# STM32_F407.net
KiCad netlist of a schematic drawn in Altium Designer
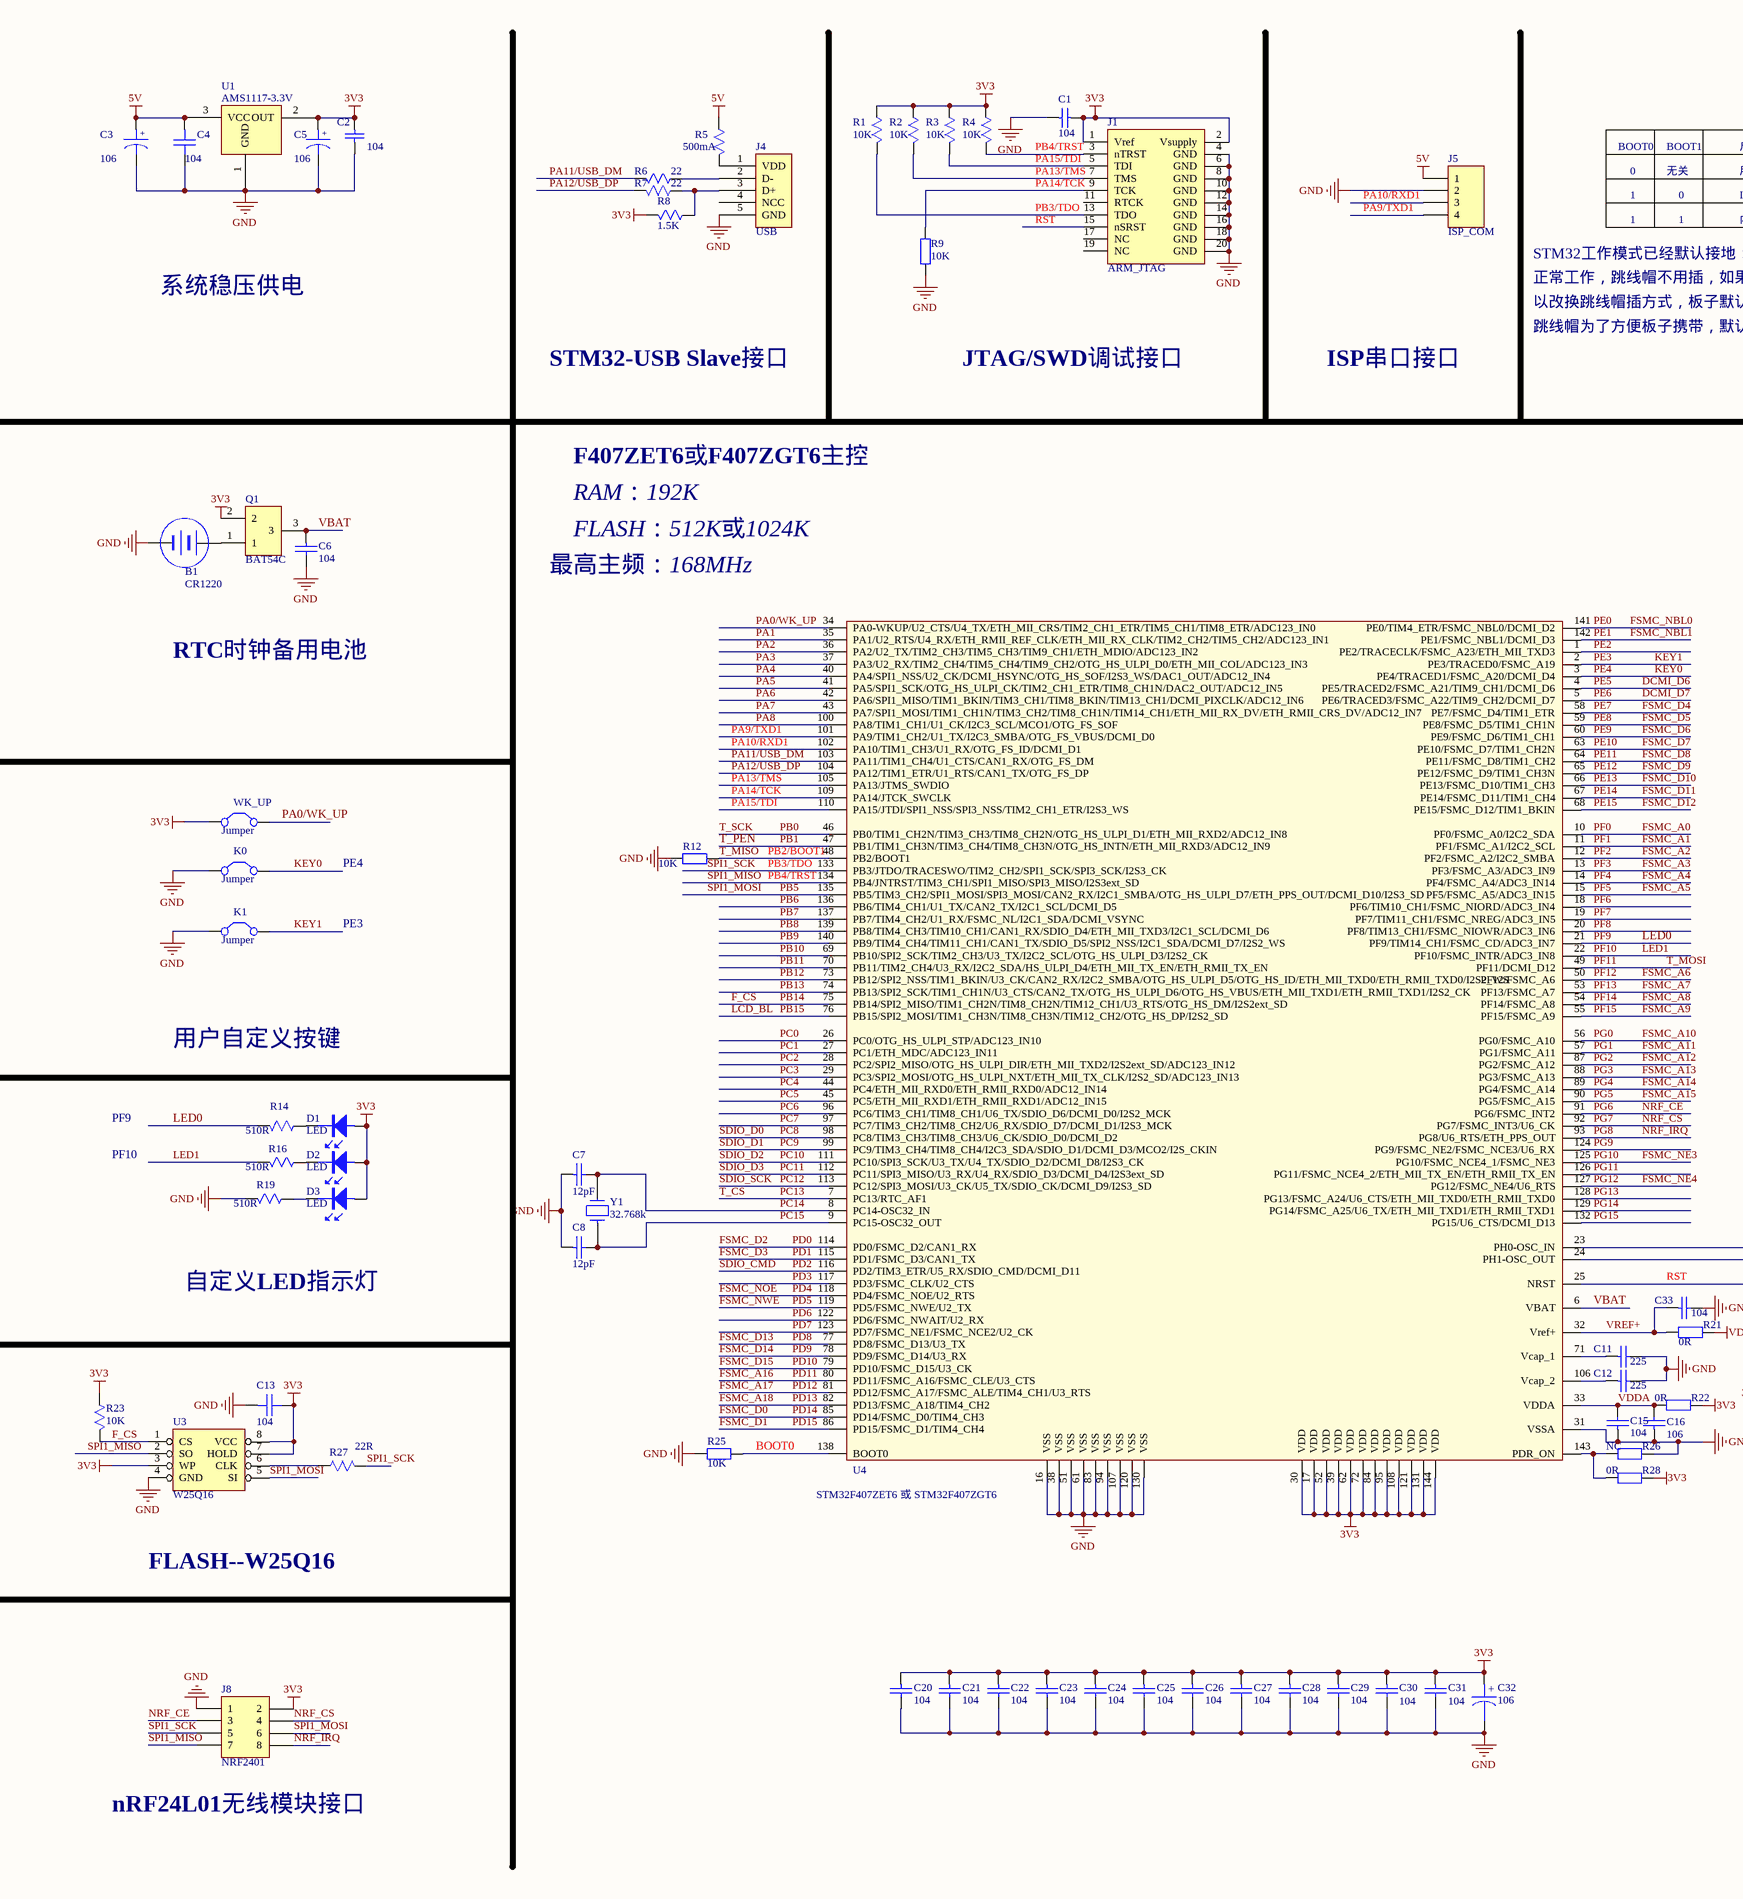
[diagram p0: STM32_F407.SchDoc, left]
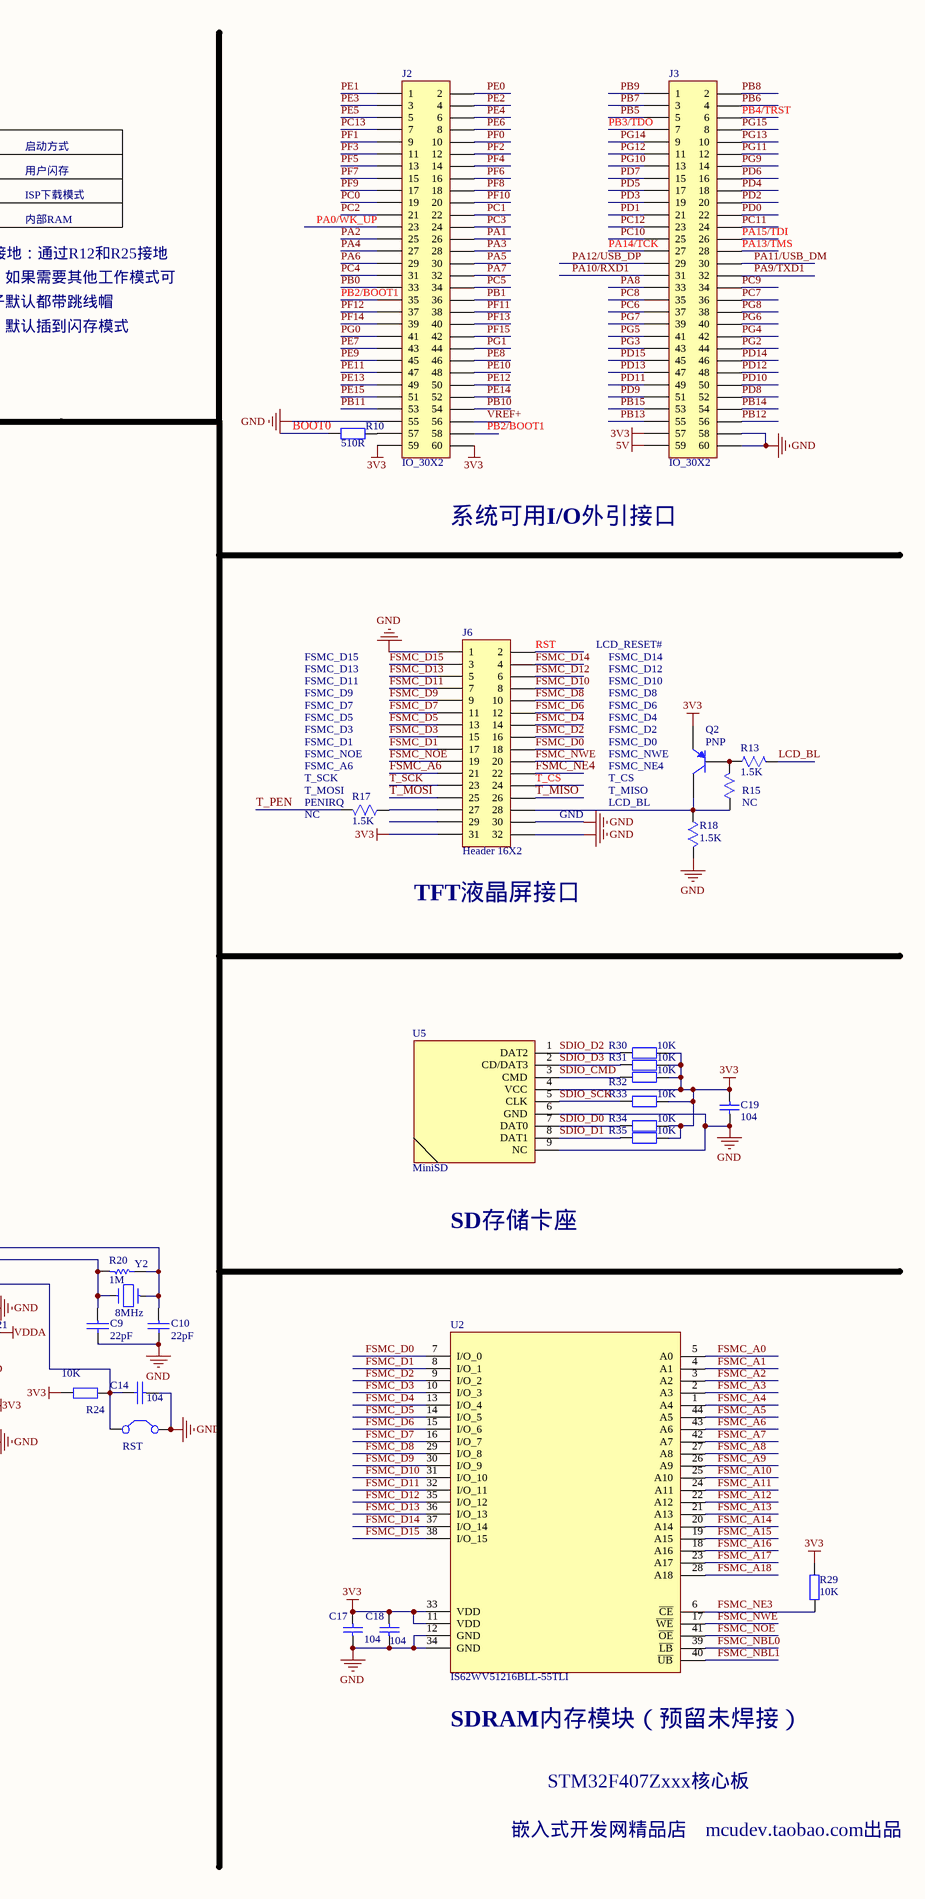
[diagram p1: STM32_F407.SchDoc, right]

(export (version "E")
  (design (tool "Eeschema 10.0.6"))
  (components
    (comp (ref "B1") (value "CR1220") (footprint "CP1220") (libsource (lib "YT1_SCH_99SE") (part "BATTERY")))
    (comp (ref "C1")
      (value "104")
      (footprint "RC0603")
      (description "Capacitor")
      (fields (field (name "PUBLISHER") "Altium Limited"))
      (libsource (lib "*") (part "Cap"))
    )
    (comp (ref "C2")
      (value "104")
      (footprint "RC0603")
      (description "Capacitor")
      (fields (field (name "PUBLISHER") "Altium Limited"))
      (libsource (lib "*") (part "Cap"))
    )
    (comp (ref "C3") (value "106") (footprint "RC0805") (libsource (lib "YT1_SCH_99SE") (part "CAP2")))
    (comp (ref "C4") (value "104") (footprint "RC0603") (libsource (lib "YT1_SCH_99SE") (part "CAP")))
    (comp (ref "C5") (value "106") (footprint "RC0805") (libsource (lib "YT1_SCH_99SE") (part "CAP2")))
    (comp (ref "C6")
      (value "104")
      (footprint "RC0603")
      (description "Capcitor")
      (libsource (lib "") (part "CAP_1"))
    )
    (comp (ref "C7")
      (value "12pF")
      (footprint "RC0603")
      (description "Capcitor")
      (libsource (lib "LXKJSJ") (part "CAP"))
    )
    (comp (ref "C8")
      (value "12pF")
      (footprint "RC0603")
      (description "Capcitor")
      (libsource (lib "LXKJSJ") (part "CAP"))
    )
    (comp (ref "C9")
      (value "22pF")
      (footprint "RC0603")
      (description "Capcitor")
      (libsource (lib "LXKJSJ") (part "CAP"))
    )
    (comp (ref "C10")
      (value "22pF")
      (footprint "RC0603")
      (description "Capcitor")
      (libsource (lib "LXKJSJ") (part "CAP"))
    )
    (comp (ref "C11")
      (value "225")
      (footprint "RC0805")
      (description "Capcitor")
      (libsource (lib "LXKJSJ") (part "CAP"))
    )
    (comp (ref "C12")
      (value "225")
      (footprint "RC0805")
      (description "Capcitor")
      (libsource (lib "LXKJSJ") (part "CAP"))
    )
    (comp (ref "C13") (value "104") (footprint "RC0603") (libsource (lib "YT1_SCH_99SE") (part "CAP")))
    (comp (ref "C14")
      (value "104")
      (footprint "RC0603")
      (description "Capcitor")
      (libsource (lib "LXKJSJ") (part "CAP"))
    )
    (comp (ref "C15")
      (value "104")
      (footprint "RC0603")
      (description "Capcitor")
      (libsource (lib "LXKJSJ") (part "CAP"))
    )
    (comp (ref "C16")
      (value "106")
      (footprint "RC0805")
      (description "Capcitor")
      (libsource (lib "LXKJSJ") (part "CAP"))
    )
    (comp (ref "C17")
      (value "104")
      (footprint "RC0603")
      (description "Capacitor")
      (fields (field (name "PUBLISHER") "Altium Limited"))
      (libsource (lib "*") (part "Cap"))
    )
    (comp (ref "C18")
      (value "104")
      (footprint "RC0603")
      (description "Capacitor")
      (fields (field (name "PUBLISHER") "Altium Limited"))
      (libsource (lib "*") (part "Cap"))
    )
    (comp (ref "C19")
      (value "104")
      (footprint "RC0603")
      (description "Capacitor (Semiconductor SIM Model)")
      (fields (field (name "PUBLISHER") "Altium Limited"))
      (libsource (lib "*") (part "Cap Semi"))
    )
    (comp (ref "C20")
      (value "104")
      (footprint "RC0603")
      (description "Capcitor")
      (libsource (lib "LXKJSJ") (part "CAP"))
    )
    (comp (ref "C21")
      (value "104")
      (footprint "RC0603")
      (description "Capcitor")
      (libsource (lib "LXKJSJ") (part "CAP"))
    )
    (comp (ref "C22")
      (value "104")
      (footprint "RC0603")
      (description "Capcitor")
      (libsource (lib "LXKJSJ") (part "CAP"))
    )
    (comp (ref "C23")
      (value "104")
      (footprint "RC0603")
      (description "Capcitor")
      (libsource (lib "LXKJSJ") (part "CAP"))
    )
    (comp (ref "C24")
      (value "104")
      (footprint "RC0603")
      (description "Capcitor")
      (libsource (lib "LXKJSJ") (part "CAP"))
    )
    (comp (ref "C25")
      (value "104")
      (footprint "RC0603")
      (description "Capcitor")
      (libsource (lib "LXKJSJ") (part "CAP"))
    )
    (comp (ref "C26")
      (value "104")
      (footprint "RC0603")
      (description "Capcitor")
      (libsource (lib "LXKJSJ") (part "CAP"))
    )
    (comp (ref "C27")
      (value "104")
      (footprint "RC0603")
      (description "Capcitor")
      (libsource (lib "LXKJSJ") (part "CAP"))
    )
    (comp (ref "C28")
      (value "104")
      (footprint "RC0603")
      (description "Capcitor")
      (libsource (lib "LXKJSJ") (part "CAP"))
    )
    (comp (ref "C29")
      (value "104")
      (footprint "RC0603")
      (description "Capcitor")
      (libsource (lib "LXKJSJ") (part "CAP"))
    )
    (comp (ref "C30")
      (value "104")
      (footprint "RC0603")
      (description "Capcitor")
      (libsource (lib "LXKJSJ") (part "CAP"))
    )
    (comp (ref "C31")
      (value "104")
      (footprint "RC0603")
      (description "Capcitor")
      (libsource (lib "LXKJSJ") (part "CAP"))
    )
    (comp (ref "C32")
      (value "106")
      (footprint "RC0805")
      (description "Capacitor")
      (libsource (lib "*") (part "CAPACITOR POL"))
    )
    (comp (ref "C33")
      (value "104")
      (footprint "RC0603")
      (description "Capcitor")
      (libsource (lib "LXKJSJ") (part "CAP"))
    )
    (comp (ref "D1") (value "LED") (footprint "LED0805") (libsource (lib "*") (part "LED")))
    (comp (ref "D2") (value "LED") (footprint "LED0805") (libsource (lib "*") (part "LED")))
    (comp (ref "D3") (value "LED") (footprint "LED0805") (libsource (lib "*") (part "LED")))
    (comp (ref "J1")
      (value "ARM_JTAG")
      (footprint "JTAG20P")
      (description "JTAG")
      (libsource (lib "LXKJSJ") (part "JTAG"))
    )
    (comp (ref "J2")
      (value "IO_30X2")
      (footprint "IDE2X30")
      (description "Header, 30-Pin, Dual row")
      (fields (field (name "PUBLISHER") "Altium Limited"))
      (libsource (lib "Miscellaneous Connectors") (part "Header 30X2"))
    )
    (comp (ref "J3")
      (value "IO_30X2")
      (footprint "IDE2X30")
      (description "Header, 30-Pin, Dual row")
      (fields (field (name "PUBLISHER") "Altium Limited"))
      (libsource (lib "Miscellaneous Connectors") (part "Header 30X2"))
    )
    (comp (ref "J4") (value "USB") (footprint "MINUSB") (libsource (lib "YT1_SCH_99SE") (part "usb")))
    (comp (ref "J5")
      (value "ISP_COM")
      (footprint "HDR1X4")
      (description "Header, 4-Pin")
      (fields (field (name "PUBLISHER") "Altium Limited"))
      (libsource (lib "Miscellaneous Connectors") (part "Header 4"))
    )
    (comp (ref "J6")
      (value "Header 16X2")
      (footprint "IDE2X16-2.54")
      (description "Header, 16-Pin, Dual row")
      (fields (field (name "PUBLISHER") "Altium Limited"))
      (libsource (lib "Miscellaneous Connectors") (part "Header 16X2"))
    )
    (comp (ref "J8")
      (value "NRF2401")
      (footprint "DIP2X4-2.54")
      (description "Header, 4-Pin, Dual row")
      (fields (field (name "PUBLISHER") "Altium Limited"))
      (libsource (lib "Miscellaneous Connectors") (part "Header 4X2"))
    )
    (comp (ref "K0")
      (value "Jumper")
      (footprint "key")
      (description "Jumper Wire")
      (fields (field (name "PUBLISHER") "Altium Limited"))
      (libsource (lib "Free Documents") (part "Jumper"))
    )
    (comp (ref "K1")
      (value "Jumper")
      (footprint "key")
      (description "Jumper Wire")
      (fields (field (name "PUBLISHER") "Altium Limited"))
      (libsource (lib "Free Documents") (part "Jumper"))
    )
    (comp (ref "Q1") (value "BAT54C") (footprint "BAT54C") (libsource (lib "Newcapec9263") (part "BAT54C")))
    (comp (ref "Q2")
      (value "PNP")
      (footprint "PNP_SOT23")
      (description "PNP Bipolar Transistor")
      (fields (field (name "PUBLISHER") "Altium Limited"))
      (libsource (lib "Miscellaneous Devices") (part "PNP"))
    )
    (comp (ref "R1") (value "10K") (footprint "RC0603") (libsource (lib "YT1_SCH_99SE") (part "RES")))
    (comp (ref "R2") (value "10K") (footprint "RC0603") (libsource (lib "YT1_SCH_99SE") (part "RES")))
    (comp (ref "R3") (value "10K") (footprint "RC0603") (libsource (lib "YT1_SCH_99SE") (part "RES")))
    (comp (ref "R4") (value "10K") (footprint "RC0603") (libsource (lib "YT1_SCH_99SE") (part "RES")))
    (comp (ref "R5") (value "500mA") (footprint "RC0805") (libsource (lib "YT1_SCH_99SE") (part "RES")))
    (comp (ref "R6") (value "22") (footprint "RC0603") (libsource (lib "YT1_SCH_99SE") (part "RES")))
    (comp (ref "R7") (value "22") (footprint "RC0603") (libsource (lib "YT1_SCH_99SE") (part "RES")))
    (comp (ref "R8") (value "1.5K") (footprint "RC0603") (libsource (lib "YT1_SCH_99SE") (part "RES")))
    (comp (ref "R9")
      (value "10K")
      (footprint "RC0603")
      (description "Resistor")
      (libsource (lib "") (part "Res2_2"))
    )
    (comp (ref "R10")
      (value "510R")
      (footprint "RC0603")
      (description "Resistor")
      (libsource (lib "") (part "Res2_3"))
    )
    (comp (ref "R12")
      (value "10K")
      (footprint "RC0603")
      (description "Resistor")
      (libsource (lib "") (part "Res2_3"))
    )
    (comp (ref "R13") (value "1.5K") (footprint "RC0603") (libsource (lib "YT1_SCH_99SE") (part "RES")))
    (comp (ref "R14") (value "510R") (footprint "RC0603") (libsource (lib "YT1_SCH_99SE") (part "RES")))
    (comp (ref "R15") (value "NC") (footprint "RC0603") (libsource (lib "YT1_SCH_99SE") (part "RES")))
    (comp (ref "R16") (value "510R") (footprint "RC0603") (libsource (lib "YT1_SCH_99SE") (part "RES")))
    (comp (ref "R17") (value "1.5K") (footprint "RC0603") (libsource (lib "YT1_SCH_99SE") (part "RES")))
    (comp (ref "R18") (value "1.5K") (footprint "RC0603") (libsource (lib "YT1_SCH_99SE") (part "RES")))
    (comp (ref "R19") (value "510R") (footprint "RC0603") (libsource (lib "YT1_SCH_99SE") (part "RES")))
    (comp (ref "R20")
      (value "1M")
      (footprint "RC0603")
      (description "Resistor")
      (libsource (lib "Miscellaneous Devices") (part "Res1"))
    )
    (comp (ref "R21")
      (value "0R")
      (footprint "RC0603")
      (description "Resistor")
      (libsource (lib "") (part "Res2_1"))
    )
    (comp (ref "R22")
      (value "0R")
      (footprint "RC0603")
      (description "Resistor")
      (libsource (lib "") (part "Res2_1"))
    )
    (comp (ref "R23") (value "10K") (footprint "RC0603") (libsource (lib "YT1_SCH_99SE") (part "RES")))
    (comp (ref "R24")
      (value "10K")
      (footprint "RC0603")
      (description "Resistor")
      (libsource (lib "") (part "Res2_3"))
    )
    (comp (ref "R25")
      (value "10K")
      (footprint "RC0603")
      (description "Resistor")
      (libsource (lib "Miscellaneous Devices") (part "Res2"))
    )
    (comp (ref "R26")
      (value "NC")
      (footprint "RC0603")
      (description "Resistor")
      (libsource (lib "") (part "Res2_1"))
    )
    (comp (ref "R27") (value "22R") (footprint "RC0603") (libsource (lib "YT1_SCH_99SE") (part "RES")))
    (comp (ref "R28")
      (value "0R")
      (footprint "RC0603")
      (description "Resistor")
      (libsource (lib "") (part "Res2_1"))
    )
    (comp (ref "R29")
      (value "10K")
      (footprint "RC0603")
      (description "Resistor")
      (libsource (lib "") (part "Res2_2"))
    )
    (comp (ref "R30")
      (value "10K")
      (footprint "RC0603")
      (description "Resistor")
      (libsource (lib "") (part "Res2_1"))
    )
    (comp (ref "R31")
      (value "10K")
      (footprint "RC0603")
      (description "Resistor")
      (libsource (lib "") (part "Res2_1"))
    )
    (comp (ref "R32")
      (value "10K")
      (footprint "RC0603")
      (description "Resistor")
      (libsource (lib "") (part "Res2_1"))
    )
    (comp (ref "R33")
      (value "10K")
      (footprint "RC0603")
      (description "Resistor")
      (libsource (lib "") (part "Res2_1"))
    )
    (comp (ref "R34")
      (value "10K")
      (footprint "RC0603")
      (description "Resistor")
      (libsource (lib "") (part "Res2_1"))
    )
    (comp (ref "R35")
      (value "10K")
      (footprint "RC0603")
      (description "Resistor")
      (libsource (lib "") (part "Res2_1"))
    )
    (comp (ref "RST")
      (value "Key")
      (footprint "key")
      (description "Jumper Wire")
      (fields (field (name "PUBLISHER") "Altium Limited"))
      (libsource (lib "Free Documents") (part "Jumper"))
    )
    (comp (ref "U1") (value "AMS1117-3.3V") (footprint "SOT223") (libsource (lib "*") (part "11")))
    (comp (ref "U2")
      (value "IS62WV51216BLL-55TLI")
      (footprint "TSOP44")
      (libsource (lib "STM32_DSO") (part "IS62WV51216BLL-55TLI"))
    )
    (comp (ref "U3") (value "W25Q16") (footprint "SOIC8P") (libsource (lib "YT1_SCH_99SE") (part "W25X16")))
    (comp (ref "U4")
      (value "STM32F407ZET6 或 STM32F407ZGT6")
      (footprint "LQFP144N")
      (description "STM32F407ZET6")
      (libsource (lib "EXPLORER") (part "STM32F407ZET6"))
    )
    (comp (ref "U5") (value "MiniSD") (footprint "TF_SD") (libsource (lib "STM32_RF") (part "MiniSD")))
    (comp (ref "WK_UP")
      (value "Jumper")
      (footprint "key")
      (description "Jumper Wire")
      (fields (field (name "PUBLISHER") "Altium Limited"))
      (libsource (lib "Free Documents") (part "Jumper"))
    )
    (comp (ref "Y1")
      (value "32.768k")
      (footprint "32.768k")
      (description "Crystal 8MHz PLUG")
      (libsource (lib "*") (part "CRYSTAL"))
    )
    (comp (ref "Y2")
      (value "8MHz")
      (footprint "SMD49S")
      (description "Crystal Oscillator")
      (libsource (lib "LXKJSJ") (part "XTAL"))
    )
  )
  (nets
    (net (code "2") (name "/BOOT0") (class "Default")
      (node (ref "R10") (pin "2") (pinfunction "2_2") (pintype "passive"))
      (node (ref "R25") (pin "1") (pinfunction "1_1") (pintype "passive"))
      (node (ref "U4") (pin "138") (pinfunction "BOOT0_138") (pintype "passive"))
    )
    (net (code "3") (name "/DCMI_D6") (class "Default")
      (node (ref "J2") (pin "5") (pinfunction "5_5") (pintype "passive"))
      (node (ref "U4") (pin "4") (pinfunction "PE5/TRACED2/FSMC_A21/TIM9_CH1/DCMI_D6_4") (pintype "passive"))
    )
    (net (code "4") (name "/DCMI_D7") (class "Default")
      (node (ref "J2") (pin "8") (pinfunction "8_8") (pintype "passive"))
      (node (ref "U4") (pin "5") (pinfunction "PE6/TRACED3/FSMC_A22/TIM9_CH2/DCMI_D7_5") (pintype "passive"))
    )
    (net (code "5") (name "/FSMC_A0") (class "Default")
      (node (ref "J2") (pin "10") (pinfunction "10_10") (pintype "passive"))
      (node (ref "U2") (pin "5") (pinfunction "A0_5") (pintype "passive"))
      (node (ref "U4") (pin "10") (pinfunction "PF0/FSMC_A0/I2C2_SDA_10") (pintype "passive"))
    )
    (net (code "6") (name "/FSMC_A1") (class "Default")
      (node (ref "J2") (pin "9") (pinfunction "9_9") (pintype "passive"))
      (node (ref "U2") (pin "4") (pinfunction "A1_4") (pintype "passive"))
      (node (ref "U4") (pin "11") (pinfunction "PF1/FSMC_A1/I2C2_SCL_11") (pintype "passive"))
    )
    (net (code "7") (name "/FSMC_A2") (class "Default")
      (node (ref "J2") (pin "12") (pinfunction "12_12") (pintype "passive"))
      (node (ref "U2") (pin "3") (pinfunction "A2_3") (pintype "passive"))
      (node (ref "U4") (pin "12") (pinfunction "PF2/FSMC_A2/I2C2_SMBA_12") (pintype "passive"))
    )
    (net (code "8") (name "/FSMC_A3") (class "Default")
      (node (ref "J2") (pin "11") (pinfunction "11_11") (pintype "passive"))
      (node (ref "U2") (pin "2") (pinfunction "A3_2") (pintype "passive"))
      (node (ref "U4") (pin "13") (pinfunction "PF3/FSMC_A3/ADC3_IN9_13") (pintype "passive"))
    )
    (net (code "9") (name "/FSMC_A4") (class "Default")
      (node (ref "J2") (pin "14") (pinfunction "14_14") (pintype "passive"))
      (node (ref "U2") (pin "1") (pinfunction "A4_1") (pintype "passive"))
      (node (ref "U4") (pin "14") (pinfunction "PF4/FSMC_A4/ADC3_IN14_14") (pintype "passive"))
    )
    (net (code "10") (name "/FSMC_A5") (class "Default")
      (node (ref "J2") (pin "13") (pinfunction "13_13") (pintype "passive"))
      (node (ref "U2") (pin "44") (pinfunction "A5_44") (pintype "passive"))
      (node (ref "U4") (pin "15") (pinfunction "PF5/FSMC_A5/ADC3_IN15_15") (pintype "passive"))
    )
    (net (code "11") (name "/FSMC_A6") (class "Default")
      (node (ref "J2") (pin "37") (pinfunction "37_37") (pintype "passive"))
      (node (ref "J6") (pin "21") (pinfunction "21_21") (pintype "passive"))
      (node (ref "U2") (pin "43") (pinfunction "A6_43") (pintype "passive"))
      (node (ref "U4") (pin "50") (pinfunction "PF12/FSMC_A6_50") (pintype "passive"))
    )
    (net (code "12") (name "/FSMC_A7") (class "Default")
      (node (ref "J2") (pin "40") (pinfunction "40_40") (pintype "passive"))
      (node (ref "U2") (pin "42") (pinfunction "A7_42") (pintype "passive"))
      (node (ref "U4") (pin "53") (pinfunction "PF13/FSMC_A7_53") (pintype "passive"))
    )
    (net (code "13") (name "/FSMC_A8") (class "Default")
      (node (ref "J2") (pin "39") (pinfunction "39_39") (pintype "passive"))
      (node (ref "U2") (pin "27") (pinfunction "A8_27") (pintype "passive"))
      (node (ref "U4") (pin "54") (pinfunction "PF14/FSMC_A8_54") (pintype "passive"))
    )
    (net (code "14") (name "/FSMC_A9") (class "Default")
      (node (ref "J2") (pin "42") (pinfunction "42_42") (pintype "passive"))
      (node (ref "U2") (pin "26") (pinfunction "A9_26") (pintype "passive"))
      (node (ref "U4") (pin "55") (pinfunction "PF15/FSMC_A9_55") (pintype "passive"))
    )
    (net (code "15") (name "/FSMC_A10") (class "Default")
      (node (ref "J2") (pin "41") (pinfunction "41_41") (pintype "passive"))
      (node (ref "U2") (pin "25") (pinfunction "A10_25") (pintype "passive"))
      (node (ref "U4") (pin "56") (pinfunction "PG0/FSMC_A10_56") (pintype "passive"))
    )
    (net (code "16") (name "/FSMC_A11") (class "Default")
      (node (ref "J2") (pin "44") (pinfunction "44_44") (pintype "passive"))
      (node (ref "U2") (pin "24") (pinfunction "A11_24") (pintype "passive"))
      (node (ref "U4") (pin "57") (pinfunction "PG1/FSMC_A11_57") (pintype "passive"))
    )
    (net (code "17") (name "/FSMC_A12") (class "Default")
      (node (ref "J3") (pin "44") (pinfunction "44_44") (pintype "passive"))
      (node (ref "U2") (pin "22") (pinfunction "A12_22") (pintype "passive"))
      (node (ref "U4") (pin "87") (pinfunction "PG2/FSMC_A12_87") (pintype "passive"))
    )
    (net (code "18") (name "/FSMC_A13") (class "Default")
      (node (ref "J3") (pin "43") (pinfunction "43_43") (pintype "passive"))
      (node (ref "U2") (pin "21") (pinfunction "A13_21") (pintype "passive"))
      (node (ref "U4") (pin "88") (pinfunction "PG3/FSMC_A13_88") (pintype "passive"))
    )
    (net (code "19") (name "/FSMC_A14") (class "Default")
      (node (ref "J3") (pin "42") (pinfunction "42_42") (pintype "passive"))
      (node (ref "U2") (pin "20") (pinfunction "A14_20") (pintype "passive"))
      (node (ref "U4") (pin "89") (pinfunction "PG4/FSMC_A14_89") (pintype "passive"))
    )
    (net (code "20") (name "/FSMC_A15") (class "Default")
      (node (ref "J3") (pin "41") (pinfunction "41_41") (pintype "passive"))
      (node (ref "U2") (pin "19") (pinfunction "A15_19") (pintype "passive"))
      (node (ref "U4") (pin "90") (pinfunction "PG5/FSMC_A15_90") (pintype "passive"))
    )
    (net (code "21") (name "/FSMC_A16") (class "Default")
      (node (ref "J3") (pin "49") (pinfunction "49_49") (pintype "passive"))
      (node (ref "U2") (pin "18") (pinfunction "A16_18") (pintype "passive"))
      (node (ref "U4") (pin "80") (pinfunction "PD11/FSMC_A16/FSMC_CLE/U3_CTS_80") (pintype "passive"))
    )
    (net (code "22") (name "/FSMC_A17") (class "Default")
      (node (ref "J3") (pin "48") (pinfunction "48_48") (pintype "passive"))
      (node (ref "U2") (pin "23") (pinfunction "A17_23") (pintype "passive"))
      (node (ref "U4") (pin "81") (pinfunction "PD12/FSMC_A17/FSMC_ALE/TIM4_CH1/U3_RTS_81") (pintype "passive"))
    )
    (net (code "23") (name "/FSMC_A18") (class "Default")
      (node (ref "J3") (pin "47") (pinfunction "47_47") (pintype "passive"))
      (node (ref "U2") (pin "28") (pinfunction "A18_28") (pintype "passive"))
      (node (ref "U4") (pin "82") (pinfunction "PD13/FSMC_A18/TIM4_CH2_82") (pintype "passive"))
    )
    (net (code "24") (name "/FSMC_D0") (class "Default")
      (node (ref "J3") (pin "46") (pinfunction "46_46") (pintype "passive"))
      (node (ref "J6") (pin "18") (pinfunction "18_18") (pintype "passive"))
      (node (ref "U2") (pin "7") (pinfunction "I/O_0_7") (pintype "passive"))
      (node (ref "U4") (pin "85") (pinfunction "PD14/FSMC_D0/TIM4_CH3_85") (pintype "passive"))
    )
    (net (code "25") (name "/FSMC_D1") (class "Default")
      (node (ref "J3") (pin "45") (pinfunction "45_45") (pintype "passive"))
      (node (ref "J6") (pin "17") (pinfunction "17_17") (pintype "passive"))
      (node (ref "U2") (pin "8") (pinfunction "I/O_1_8") (pintype "passive"))
      (node (ref "U4") (pin "86") (pinfunction "PD15/FSMC_D1/TIM4_CH4_86") (pintype "passive"))
    )
    (net (code "26") (name "/FSMC_D2") (class "Default")
      (node (ref "J3") (pin "22") (pinfunction "22_22") (pintype "passive"))
      (node (ref "J6") (pin "16") (pinfunction "16_16") (pintype "passive"))
      (node (ref "U2") (pin "9") (pinfunction "I/O_2_9") (pintype "passive"))
      (node (ref "U4") (pin "114") (pinfunction "PD0/FSMC_D2/CAN1_RX_114") (pintype "passive"))
    )
    (net (code "27") (name "/FSMC_D3") (class "Default")
      (node (ref "J3") (pin "21") (pinfunction "21_21") (pintype "passive"))
      (node (ref "J6") (pin "15") (pinfunction "15_15") (pintype "passive"))
      (node (ref "U2") (pin "10") (pinfunction "I/O_3_10") (pintype "passive"))
      (node (ref "U4") (pin "115") (pinfunction "PD1/FSMC_D3/CAN1_TX_115") (pintype "passive"))
    )
    (net (code "28") (name "/FSMC_D4") (class "Default")
      (node (ref "J2") (pin "43") (pinfunction "43_43") (pintype "passive"))
      (node (ref "J6") (pin "14") (pinfunction "14_14") (pintype "passive"))
      (node (ref "U2") (pin "13") (pinfunction "I/O_4_13") (pintype "passive"))
      (node (ref "U4") (pin "58") (pinfunction "PE7/FSMC_D4/TIM1_ETR_58") (pintype "passive"))
    )
    (net (code "29") (name "/FSMC_D5") (class "Default")
      (node (ref "J2") (pin "46") (pinfunction "46_46") (pintype "passive"))
      (node (ref "J6") (pin "13") (pinfunction "13_13") (pintype "passive"))
      (node (ref "U2") (pin "14") (pinfunction "I/O_5_14") (pintype "passive"))
      (node (ref "U4") (pin "59") (pinfunction "PE8/FSMC_D5/TIM1_CH1N_59") (pintype "passive"))
    )
    (net (code "30") (name "/FSMC_D6") (class "Default")
      (node (ref "J2") (pin "45") (pinfunction "45_45") (pintype "passive"))
      (node (ref "J6") (pin "12") (pinfunction "12_12") (pintype "passive"))
      (node (ref "U2") (pin "15") (pinfunction "I/O_6_15") (pintype "passive"))
      (node (ref "U4") (pin "60") (pinfunction "PE9/FSMC_D6/TIM1_CH1_60") (pintype "passive"))
    )
    (net (code "31") (name "/FSMC_D7") (class "Default")
      (node (ref "J2") (pin "48") (pinfunction "48_48") (pintype "passive"))
      (node (ref "J6") (pin "11") (pinfunction "11_11") (pintype "passive"))
      (node (ref "U2") (pin "16") (pinfunction "I/O_7_16") (pintype "passive"))
      (node (ref "U4") (pin "63") (pinfunction "PE10/FSMC_D7/TIM1_CH2N_63") (pintype "passive"))
    )
    (net (code "32") (name "/FSMC_D8") (class "Default")
      (node (ref "J2") (pin "47") (pinfunction "47_47") (pintype "passive"))
      (node (ref "J6") (pin "10") (pinfunction "10_10") (pintype "passive"))
      (node (ref "U2") (pin "29") (pinfunction "I/O_8_29") (pintype "passive"))
      (node (ref "U4") (pin "64") (pinfunction "PE11/FSMC_D8/TIM1_CH2_64") (pintype "passive"))
    )
    (net (code "33") (name "/FSMC_D9") (class "Default")
      (node (ref "J2") (pin "50") (pinfunction "50_50") (pintype "passive"))
      (node (ref "J6") (pin "9") (pinfunction "9_9") (pintype "passive"))
      (node (ref "U2") (pin "30") (pinfunction "I/O_9_30") (pintype "passive"))
      (node (ref "U4") (pin "65") (pinfunction "PE12/FSMC_D9/TIM1_CH3N_65") (pintype "passive"))
    )
    (net (code "34") (name "/FSMC_D10") (class "Default")
      (node (ref "J2") (pin "49") (pinfunction "49_49") (pintype "passive"))
      (node (ref "J6") (pin "8") (pinfunction "8_8") (pintype "passive"))
      (node (ref "U2") (pin "31") (pinfunction "I/O_10_31") (pintype "passive"))
      (node (ref "U4") (pin "66") (pinfunction "PE13/FSMC_D10/TIM1_CH3_66") (pintype "passive"))
    )
    (net (code "35") (name "/FSMC_D11") (class "Default")
      (node (ref "J2") (pin "52") (pinfunction "52_52") (pintype "passive"))
      (node (ref "J6") (pin "7") (pinfunction "7_7") (pintype "passive"))
      (node (ref "U2") (pin "32") (pinfunction "I/O_11_32") (pintype "passive"))
      (node (ref "U4") (pin "67") (pinfunction "PE14/FSMC_D11/TIM1_CH4_67") (pintype "passive"))
    )
    (net (code "36") (name "/FSMC_D12") (class "Default")
      (node (ref "J2") (pin "51") (pinfunction "51_51") (pintype "passive"))
      (node (ref "J6") (pin "6") (pinfunction "6_6") (pintype "passive"))
      (node (ref "U2") (pin "35") (pinfunction "I/O_12_35") (pintype "passive"))
      (node (ref "U4") (pin "68") (pinfunction "PE15/FSMC_D12/TIM1_BKIN_68") (pintype "passive"))
    )
    (net (code "37") (name "/FSMC_D13") (class "Default")
      (node (ref "J3") (pin "52") (pinfunction "52_52") (pintype "passive"))
      (node (ref "J6") (pin "5") (pinfunction "5_5") (pintype "passive"))
      (node (ref "U2") (pin "36") (pinfunction "I/O_13_36") (pintype "passive"))
      (node (ref "U4") (pin "77") (pinfunction "PD8/FSMC_D13/U3_TX_77") (pintype "passive"))
    )
    (net (code "38") (name "/FSMC_D14") (class "Default")
      (node (ref "J3") (pin "51") (pinfunction "51_51") (pintype "passive"))
      (node (ref "J6") (pin "4") (pinfunction "4_4") (pintype "passive"))
      (node (ref "U2") (pin "37") (pinfunction "I/O_14_37") (pintype "passive"))
      (node (ref "U4") (pin "78") (pinfunction "PD9/FSMC_D14/U3_RX_78") (pintype "passive"))
    )
    (net (code "39") (name "/FSMC_D15") (class "Default")
      (node (ref "J3") (pin "50") (pinfunction "50_50") (pintype "passive"))
      (node (ref "J6") (pin "3") (pinfunction "3_3") (pintype "passive"))
      (node (ref "U2") (pin "38") (pinfunction "I/O_15_38") (pintype "passive"))
      (node (ref "U4") (pin "79") (pinfunction "PD10/FSMC_D15/U3_CK_79") (pintype "passive"))
    )
    (net (code "40") (name "/FSMC_NBL0") (class "Default")
      (node (ref "J2") (pin "2") (pinfunction "2_2") (pintype "passive"))
      (node (ref "U2") (pin "39") (pinfunction "~{LB}_39") (pintype "passive"))
      (node (ref "U4") (pin "141") (pinfunction "PE0/TIM4_ETR/FSMC_NBL0/DCMI_D2_141") (pintype "passive"))
    )
    (net (code "41") (name "/FSMC_NBL1") (class "Default")
      (node (ref "J2") (pin "1") (pinfunction "1_1") (pintype "passive"))
      (node (ref "U2") (pin "40") (pinfunction "~{UB}_40") (pintype "passive"))
      (node (ref "U4") (pin "142") (pinfunction "PE1/FSMC_NBL1/DCMI_D3_142") (pintype "passive"))
    )
    (net (code "42") (name "/FSMC_NE3") (class "Default")
      (node (ref "J3") (pin "13") (pinfunction "13_13") (pintype "passive"))
      (node (ref "R29") (pin "1") (pinfunction "1_1") (pintype "passive"))
      (node (ref "U2") (pin "6") (pinfunction "~{CE}_6") (pintype "passive"))
      (node (ref "U4") (pin "125") (pinfunction "PG10/FSMC_NCE4_1/FSMC_NE3_125") (pintype "passive"))
    )
    (net (code "43") (name "/FSMC_NE4") (class "Default")
      (node (ref "J3") (pin "11") (pinfunction "11_11") (pintype "passive"))
      (node (ref "J6") (pin "22") (pinfunction "22_22") (pintype "passive"))
      (node (ref "U4") (pin "127") (pinfunction "PG12/FSMC_NE4/U6_RTS_127") (pintype "passive"))
    )
    (net (code "44") (name "/FSMC_NOE") (class "Default")
      (node (ref "J3") (pin "18") (pinfunction "18_18") (pintype "passive"))
      (node (ref "J6") (pin "19") (pinfunction "19_19") (pintype "passive"))
      (node (ref "U2") (pin "41") (pinfunction "~{OE}_41") (pintype "passive"))
      (node (ref "U4") (pin "118") (pinfunction "PD4/FSMC_NOE/U2_RTS_118") (pintype "passive"))
    )
    (net (code "45") (name "/FSMC_NWE") (class "Default")
      (node (ref "J3") (pin "17") (pinfunction "17_17") (pintype "passive"))
      (node (ref "J6") (pin "20") (pinfunction "20_20") (pintype "passive"))
      (node (ref "U2") (pin "17") (pinfunction "~{WE}_17") (pintype "passive"))
      (node (ref "U4") (pin "119") (pinfunction "PD5/FSMC_NWE/U2_TX_119") (pintype "passive"))
    )
    (net (code "46") (name "/F_CS") (class "Default")
      (node (ref "J3") (pin "54") (pinfunction "54_54") (pintype "passive"))
      (node (ref "R23") (pin "2") (pinfunction "2_2") (pintype "passive"))
      (node (ref "U3") (pin "1") (pinfunction "CS_1") (pintype "passive"))
      (node (ref "U4") (pin "75") (pinfunction "PB14/SPI2_MISO/TIM1_CH2N/TIM8_CH2N/TIM12_CH1/U3_RTS/OTG_HS_DM/I2S2ext_SD_75") (pintype "passive"))
    )
    (net (code "47") (name "/KEY0") (class "Default")
      (node (ref "J2") (pin "6") (pinfunction "6_6") (pintype "passive"))
      (node (ref "K0") (pin "2") (pinfunction "C2_2") (pintype "passive"))
      (node (ref "U4") (pin "3") (pinfunction "PE4/TRACED1/FSMC_A20/DCMI_D4_3") (pintype "passive"))
    )
    (net (code "48") (name "/KEY1") (class "Default")
      (node (ref "J2") (pin "3") (pinfunction "3_3") (pintype "passive"))
      (node (ref "K1") (pin "2") (pinfunction "C2_2") (pintype "passive"))
      (node (ref "U4") (pin "2") (pinfunction "PE3/TRACED0/FSMC_A19_2") (pintype "passive"))
    )
    (net (code "49") (name "/LCD_BL") (class "Default")
      (node (ref "J3") (pin "53") (pinfunction "53_53") (pintype "passive"))
      (node (ref "R13") (pin "2") (pinfunction "2_2") (pintype "passive"))
      (node (ref "U4") (pin "76") (pinfunction "PB15/SPI2_MOSI/TIM1_CH3N/TIM8_CH3N/TIM12_CH2/OTG_HS_DP/I2S2_SD_76") (pintype "passive"))
    )
    (net (code "50") (name "/LED0") (class "Default")
      (node (ref "J2") (pin "17") (pinfunction "17_17") (pintype "passive"))
      (node (ref "R14") (pin "2") (pinfunction "2_2") (pintype "passive"))
      (node (ref "U4") (pin "21") (pinfunction "PF9/TIM14_CH1/FSMC_CD/ADC3_IN7_21") (pintype "passive"))
    )
    (net (code "51") (name "/LED1") (class "Default")
      (node (ref "J2") (pin "20") (pinfunction "20_20") (pintype "passive"))
      (node (ref "R16") (pin "2") (pinfunction "2_2") (pintype "passive"))
      (node (ref "U4") (pin "22") (pinfunction "PF10/FSMC_INTR/ADC3_IN8_22") (pintype "passive"))
    )
    (net (code "52") (name "/NRF_CE") (class "Default")
      (node (ref "J3") (pin "40") (pinfunction "40_40") (pintype "passive"))
      (node (ref "J8") (pin "3") (pinfunction "3_3") (pintype "passive"))
      (node (ref "U4") (pin "91") (pinfunction "PG6/FSMC_INT2_91") (pintype "passive"))
    )
    (net (code "53") (name "/NRF_CS") (class "Default")
      (node (ref "J3") (pin "39") (pinfunction "39_39") (pintype "passive"))
      (node (ref "J8") (pin "4") (pinfunction "4_4") (pintype "passive"))
      (node (ref "U4") (pin "92") (pinfunction "PG7/FSMC_INT3/U6_CK_92") (pintype "passive"))
    )
    (net (code "54") (name "/NRF_IRQ") (class "Default")
      (node (ref "J3") (pin "38") (pinfunction "38_38") (pintype "passive"))
      (node (ref "J8") (pin "8") (pinfunction "8_8") (pintype "passive"))
      (node (ref "U4") (pin "93") (pinfunction "PG8/U6_RTS/ETH_PPS_OUT_93") (pintype "passive"))
    )
    (net (code "55") (name "/PA0{slash}WK_UP") (class "Default")
      (node (ref "J2") (pin "23") (pinfunction "23_23") (pintype "passive"))
      (node (ref "U4") (pin "34") (pinfunction "PA0-WKUP/U2_CTS/U4_TX/ETH_MII_CRS/TIM2_CH1_ETR/TIM5_CH1/TIM8_ETR/ADC123_IN0_34") (pintype "passive"))
      (node (ref "WK_UP") (pin "2") (pinfunction "C2_2") (pintype "passive"))
    )
    (net (code "56") (name "/PA1") (class "Default")
      (node (ref "J2") (pin "26") (pinfunction "26_26") (pintype "passive"))
      (node (ref "U4") (pin "35") (pinfunction "PA1/U2_RTS/U4_RX/ETH_RMII_REF_CLK/ETH_MII_RX_CLK/TIM2_CH2/TIM5_CH2/ADC123_IN1_35") (pintype "passive"))
    )
    (net (code "57") (name "/PA2") (class "Default")
      (node (ref "J2") (pin "25") (pinfunction "25_25") (pintype "passive"))
      (node (ref "U4") (pin "36") (pinfunction "PA2/U2_TX/TIM2_CH3/TIM5_CH3/TIM9_CH1/ETH_MDIO/ADC123_IN2_36") (pintype "passive"))
    )
    (net (code "58") (name "/PA3") (class "Default")
      (node (ref "J2") (pin "28") (pinfunction "28_28") (pintype "passive"))
      (node (ref "U4") (pin "37") (pinfunction "PA3/U2_RX/TIM2_CH4/TIM5_CH4/TIM9_CH2/OTG_HS_ULPI_D0/ETH_MII_COL/ADC123_IN3_37") (pintype "passive"))
    )
    (net (code "59") (name "/PA4") (class "Default")
      (node (ref "J2") (pin "27") (pinfunction "27_27") (pintype "passive"))
      (node (ref "U4") (pin "40") (pinfunction "PA4/SPI1_NSS/U2_CK/DCMI_HSYNC/OTG_HS_SOF/I2S3_WS/DAC1_OUT/ADC12_IN4_40") (pintype "passive"))
    )
    (net (code "60") (name "/PA5") (class "Default")
      (node (ref "J2") (pin "30") (pinfunction "30_30") (pintype "passive"))
      (node (ref "U4") (pin "41") (pinfunction "PA5/SPI1_SCK/OTG_HS_ULPI_CK/TIM2_CH1_ETR/TIM8_CH1N/DAC2_OUT/ADC12_IN5_41") (pintype "passive"))
    )
    (net (code "61") (name "/PA6") (class "Default")
      (node (ref "J2") (pin "29") (pinfunction "29_29") (pintype "passive"))
      (node (ref "U4") (pin "42") (pinfunction "PA6/SPI1_MISO/TIM1_BKIN/TIM3_CH1/TIM8_BKIN/TIM13_CH1/DCMI_PIXCLK/ADC12_IN6_42") (pintype "passive"))
    )
    (net (code "62") (name "/PA7") (class "Default")
      (node (ref "J2") (pin "32") (pinfunction "32_32") (pintype "passive"))
      (node (ref "U4") (pin "43") (pinfunction "PA7/SPI1_MOSI/TIM1_CH1N/TIM3_CH2/TIM8_CH1N/TIM14_CH1/ETH_MII_RX_DV/ETH_RMII_CRS_DV/ADC12_IN7_43") (pintype "passive"))
    )
    (net (code "63") (name "/PA8") (class "Default")
      (node (ref "J3") (pin "33") (pinfunction "33_33") (pintype "passive"))
      (node (ref "U4") (pin "100") (pinfunction "PA8/TIM1_CH1/U1_CK/I2C3_SCL/MCO1/OTG_FS_SOF_100") (pintype "passive"))
    )
    (net (code "64") (name "/PA9{slash}TXD1") (class "Default")
      (node (ref "J3") (pin "32") (pinfunction "32_32") (pintype "passive"))
      (node (ref "J5") (pin "4") (pinfunction "4_4") (pintype "passive"))
      (node (ref "U4") (pin "101") (pinfunction "PA9/TIM1_CH2/U1_TX/I2C3_SMBA/OTG_FS_VBUS/DCMI_D0_101") (pintype "passive"))
    )
    (net (code "65") (name "/PA10{slash}RXD1") (class "Default")
      (node (ref "J3") (pin "31") (pinfunction "31_31") (pintype "passive"))
      (node (ref "J5") (pin "3") (pinfunction "3_3") (pintype "passive"))
      (node (ref "U4") (pin "102") (pinfunction "PA10/TIM1_CH3/U1_RX/OTG_FS_ID/DCMI_D1_102") (pintype "passive"))
    )
    (net (code "66") (name "/PA11{slash}USB_DM") (class "Default")
      (node (ref "J3") (pin "30") (pinfunction "30_30") (pintype "passive"))
      (node (ref "R6") (pin "2") (pinfunction "2_2") (pintype "passive"))
      (node (ref "U4") (pin "103") (pinfunction "PA11/TIM1_CH4/U1_CTS/CAN1_RX/OTG_FS_DM_103") (pintype "passive"))
    )
    (net (code "67") (name "/PA12{slash}USB_DP") (class "Default")
      (node (ref "J3") (pin "29") (pinfunction "29_29") (pintype "passive"))
      (node (ref "R7") (pin "2") (pinfunction "2_2") (pintype "passive"))
      (node (ref "U4") (pin "104") (pinfunction "PA12/TIM1_ETR/U1_RTS/CAN1_TX/OTG_FS_DP_104") (pintype "passive"))
    )
    (net (code "68") (name "/PA13{slash}TMS") (class "Default")
      (node (ref "J1") (pin "7") (pinfunction "TMS_7") (pintype "passive"))
      (node (ref "J3") (pin "28") (pinfunction "28_28") (pintype "passive"))
      (node (ref "R2") (pin "2") (pinfunction "2_2") (pintype "passive"))
      (node (ref "U4") (pin "105") (pinfunction "PA13/JTMS_SWDIO_105") (pintype "passive"))
    )
    (net (code "69") (name "/PA14{slash}TCK") (class "Default")
      (node (ref "J1") (pin "9") (pinfunction "TCK_9") (pintype "passive"))
      (node (ref "J3") (pin "27") (pinfunction "27_27") (pintype "passive"))
      (node (ref "R9") (pin "2") (pinfunction "2_2") (pintype "passive"))
      (node (ref "U4") (pin "109") (pinfunction "PA14/JTCK_SWCLK_109") (pintype "passive"))
    )
    (net (code "70") (name "/PA15{slash}TDI") (class "Default")
      (node (ref "J1") (pin "5") (pinfunction "TDI_5") (pintype "passive"))
      (node (ref "J3") (pin "26") (pinfunction "26_26") (pintype "passive"))
      (node (ref "R3") (pin "2") (pinfunction "2_2") (pintype "passive"))
      (node (ref "U4") (pin "110") (pinfunction "PA15/JTDI/SPI1_NSS/SPI3_NSS/TIM2_CH1_ETR/I2S3_WS_110") (pintype "passive"))
    )
    (net (code "71") (name "/PB0") (class "Default")
      (node (ref "J2") (pin "33") (pinfunction "33_33") (pintype "passive"))
      (node (ref "J6") (pin "23") (pinfunction "23_23") (pintype "passive"))
      (node (ref "U4") (pin "46") (pinfunction "PB0/TIM1_CH2N/TIM3_CH3/TIM8_CH2N/OTG_HS_ULPI_D1/ETH_MII_RXD2/ADC12_IN8_46") (pintype "passive"))
    )
    (net (code "72") (name "/PB1") (class "Default")
      (node (ref "J2") (pin "36") (pinfunction "36_36") (pintype "passive"))
      (node (ref "R17") (pin "2") (pinfunction "2_2") (pintype "passive"))
      (node (ref "U4") (pin "47") (pinfunction "PB1/TIM1_CH3N/TIM3_CH4/TIM8_CH3N/OTG_HS_INTN/ETH_MII_RXD3/ADC12_IN9_47") (pintype "passive"))
    )
    (net (code "73") (name "/PB2{slash}BOOT1") (class "Default")
      (node (ref "J2") (pin "35") (pinfunction "35_35") (pintype "passive"))
      (node (ref "J2") (pin "58") (pinfunction "58_58") (pintype "passive"))
      (node (ref "J6") (pin "26") (pinfunction "26_26") (pintype "passive"))
      (node (ref "R12") (pin "1") (pinfunction "1_1") (pintype "passive"))
      (node (ref "U4") (pin "48") (pinfunction "PB2/BOOT1_48") (pintype "passive"))
    )
    (net (code "74") (name "/PB3{slash}TDO") (class "Default")
      (node (ref "J1") (pin "13") (pinfunction "TDO_13") (pintype "passive"))
      (node (ref "J3") (pin "7") (pinfunction "7_7") (pintype "passive"))
      (node (ref "J8") (pin "5") (pinfunction "5_5") (pintype "passive"))
      (node (ref "R1") (pin "2") (pinfunction "2_2") (pintype "passive"))
      (node (ref "R27") (pin "2") (pinfunction "2_2") (pintype "passive"))
      (node (ref "U4") (pin "133") (pinfunction "PB3/JTDO/TRACESWO/TIM2_CH2/SPI1_SCK/SPI3_SCK/I2S3_CK_133") (pintype "passive"))
    )
    (net (code "75") (name "/PB4{slash}TRST") (class "Default")
      (node (ref "J1") (pin "3") (pinfunction "nTRST_3") (pintype "passive"))
      (node (ref "J3") (pin "6") (pinfunction "6_6") (pintype "passive"))
      (node (ref "J8") (pin "7") (pinfunction "7_7") (pintype "passive"))
      (node (ref "R4") (pin "2") (pinfunction "2_2") (pintype "passive"))
      (node (ref "U3") (pin "2") (pinfunction "SO_2") (pintype "passive"))
      (node (ref "U4") (pin "134") (pinfunction "PB4/JNTRST/TIM3_CH1/SPI1_MISO/SPI3_MISO/I2S3ext_SD_134") (pintype "passive"))
    )
    (net (code "76") (name "/PB5") (class "Default")
      (node (ref "J3") (pin "5") (pinfunction "5_5") (pintype "passive"))
      (node (ref "J8") (pin "6") (pinfunction "6_6") (pintype "passive"))
      (node (ref "U3") (pin "5") (pinfunction "SI_5") (pintype "passive"))
      (node (ref "U4") (pin "135") (pinfunction "PB5/TIM3_CH2/SPI1_MOSI/SPI3_MOSI/CAN2_RX/I2C1_SMBA/OTG_HS_ULPI_D7/ETH_PPS_OUT/DCMI_D10/I2S3_SD_135") (pintype "passive"))
    )
    (net (code "77") (name "/PB6") (class "Default")
      (node (ref "J3") (pin "4") (pinfunction "4_4") (pintype "passive"))
      (node (ref "U4") (pin "136") (pinfunction "PB6/TIM4_CH1/U1_TX/CAN2_TX/I2C1_SCL/DCMI_D5_136") (pintype "passive"))
    )
    (net (code "78") (name "/PB7") (class "Default")
      (node (ref "J3") (pin "3") (pinfunction "3_3") (pintype "passive"))
      (node (ref "U4") (pin "137") (pinfunction "PB7/TIM4_CH2/U1_RX/FSMC_NL/I2C1_SDA/DCMI_VSYNC_137") (pintype "passive"))
    )
    (net (code "79") (name "/PB8") (class "Default")
      (node (ref "J3") (pin "2") (pinfunction "2_2") (pintype "passive"))
      (node (ref "U4") (pin "139") (pinfunction "PB8/TIM4_CH3/TIM10_CH1/CAN1_RX/SDIO_D4/ETH_MII_TXD3/I2C1_SCL/DCMI_D6_139") (pintype "passive"))
    )
    (net (code "80") (name "/PB9") (class "Default")
      (node (ref "J3") (pin "1") (pinfunction "1_1") (pintype "passive"))
      (node (ref "U4") (pin "140") (pinfunction "PB9/TIM4_CH4/TIM11_CH1/CAN1_TX/SDIO_D5/SPI2_NSS/I2C1_SDA/DCMI_D7/I2S2_WS_140") (pintype "passive"))
    )
    (net (code "81") (name "/PB10") (class "Default")
      (node (ref "J2") (pin "54") (pinfunction "54_54") (pintype "passive"))
      (node (ref "U4") (pin "69") (pinfunction "PB10/SPI2_SCK/TIM2_CH3/U3_TX/I2C2_SCL/OTG_HS_ULPI_D3/I2S2_CK_69") (pintype "passive"))
    )
    (net (code "82") (name "/PB11") (class "Default")
      (node (ref "J2") (pin "53") (pinfunction "53_53") (pintype "passive"))
      (node (ref "U4") (pin "70") (pinfunction "PB11/TIM2_CH4/U3_RX/I2C2_SDA/HS_ULPI_D4/ETH_MII_TX_EN/ETH_RMII_TX_EN_70") (pintype "passive"))
    )
    (net (code "83") (name "/PB12") (class "Default")
      (node (ref "J3") (pin "56") (pinfunction "56_56") (pintype "passive"))
      (node (ref "U4") (pin "73") (pinfunction "PB12/SPI2_NSS/TIM1_BKIN/U3_CK/CAN2_RX/I2C2_SMBA/OTG_HS_ULPI_D5/OTG_HS_ID/ETH_MII_TXD0/ETH_RMII_TXD0/I2S2_WS_73") (pintype "passive"))
    )
    (net (code "84") (name "/PB13") (class "Default")
      (node (ref "J3") (pin "55") (pinfunction "55_55") (pintype "passive"))
      (node (ref "U4") (pin "74") (pinfunction "PB13/SPI2_SCK/TIM1_CH1N/U3_CTS/CAN2_TX/OTG_HS_ULPI_D6/OTG_HS_VBUS/ETH_MII_TXD1/ETH_RMII_TXD1/I2S2_CK_74") (pintype "passive"))
    )
    (net (code "85") (name "/PC0") (class "Default")
      (node (ref "J2") (pin "19") (pinfunction "19_19") (pintype "passive"))
      (node (ref "U4") (pin "26") (pinfunction "PC0/OTG_HS_ULPI_STP/ADC123_IN10_26") (pintype "passive"))
    )
    (net (code "86") (name "/PC1") (class "Default")
      (node (ref "J2") (pin "22") (pinfunction "22_22") (pintype "passive"))
      (node (ref "U4") (pin "27") (pinfunction "PC1/ETH_MDC/ADC123_IN11_27") (pintype "passive"))
    )
    (net (code "87") (name "/PC2") (class "Default")
      (node (ref "J2") (pin "21") (pinfunction "21_21") (pintype "passive"))
      (node (ref "U4") (pin "28") (pinfunction "PC2/SPI2_MISO/OTG_HS_ULPI_DIR/ETH_MII_TXD2/I2S2ext_SD/ADC123_IN12_28") (pintype "passive"))
    )
    (net (code "88") (name "/PC3") (class "Default")
      (node (ref "J2") (pin "24") (pinfunction "24_24") (pintype "passive"))
      (node (ref "U4") (pin "29") (pinfunction "PC3/SPI2_MOSI/OTG_HS_ULPI_NXT/ETH_MII_TX_CLK/I2S2_SD/ADC123_IN13_29") (pintype "passive"))
    )
    (net (code "89") (name "/PC4") (class "Default")
      (node (ref "J2") (pin "31") (pinfunction "31_31") (pintype "passive"))
      (node (ref "U4") (pin "44") (pinfunction "PC4/ETH_MII_RXD0/ETH_RMII_RXD0/ADC12_IN14_44") (pintype "passive"))
    )
    (net (code "90") (name "/PC5") (class "Default")
      (node (ref "J2") (pin "34") (pinfunction "34_34") (pintype "passive"))
      (node (ref "U4") (pin "45") (pinfunction "PC5/ETH_MII_RXD1/ETH_RMII_RXD1/ADC12_IN15_45") (pintype "passive"))
    )
    (net (code "91") (name "/PC6") (class "Default")
      (node (ref "J3") (pin "37") (pinfunction "37_37") (pintype "passive"))
      (node (ref "U4") (pin "96") (pinfunction "PC6/TIM3_CH1/TIM8_CH1/U6_TX/SDIO_D6/DCMI_D0/I2S2_MCK_96") (pintype "passive"))
    )
    (net (code "92") (name "/PC7") (class "Default")
      (node (ref "J3") (pin "36") (pinfunction "36_36") (pintype "passive"))
      (node (ref "U4") (pin "97") (pinfunction "PC7/TIM3_CH2/TIM8_CH2/U6_RX/SDIO_D7/DCMI_D1/I2S3_MCK_97") (pintype "passive"))
    )
    (net (code "93") (name "/PC8") (class "Default")
      (node (ref "J3") (pin "35") (pinfunction "35_35") (pintype "passive"))
      (node (ref "R34") (pin "1") (pinfunction "1_1") (pintype "passive"))
      (node (ref "U4") (pin "98") (pinfunction "PC8/TIM3_CH3/TIM8_CH3/U6_CK/SDIO_D0/DCMI_D2_98") (pintype "passive"))
      (node (ref "U5") (pin "7") (pinfunction "DAT0_7") (pintype "passive"))
    )
    (net (code "94") (name "/PC9") (class "Default")
      (node (ref "J3") (pin "34") (pinfunction "34_34") (pintype "passive"))
      (node (ref "R35") (pin "1") (pinfunction "1_1") (pintype "passive"))
      (node (ref "U4") (pin "99") (pinfunction "PC9/TIM3_CH4/TIM8_CH4/I2C3_SDA/SDIO_D1/DCMI_D3/MCO2/I2S_CKIN_99") (pintype "passive"))
      (node (ref "U5") (pin "8") (pinfunction "DAT1_8") (pintype "passive"))
    )
    (net (code "95") (name "/PC10") (class "Default")
      (node (ref "J3") (pin "25") (pinfunction "25_25") (pintype "passive"))
      (node (ref "R30") (pin "1") (pinfunction "1_1") (pintype "passive"))
      (node (ref "U4") (pin "111") (pinfunction "PC10/SPI3_SCK/U3_TX/U4_TX/SDIO_D2/DCMI_D8/I2S3_CK_111") (pintype "passive"))
      (node (ref "U5") (pin "1") (pinfunction "DAT2_1") (pintype "passive"))
    )
    (net (code "96") (name "/PC11") (class "Default")
      (node (ref "J3") (pin "24") (pinfunction "24_24") (pintype "passive"))
      (node (ref "R31") (pin "1") (pinfunction "1_1") (pintype "passive"))
      (node (ref "U4") (pin "112") (pinfunction "PC11/SPI3_MISO/U3_RX/U4_RX/SDIO_D3/DCMI_D4/I2S3ext_SD_112") (pintype "passive"))
      (node (ref "U5") (pin "2") (pinfunction "CD/DAT3_2") (pintype "passive"))
    )
    (net (code "97") (name "/PC12") (class "Default")
      (node (ref "J3") (pin "23") (pinfunction "23_23") (pintype "passive"))
      (node (ref "R33") (pin "1") (pinfunction "1_1") (pintype "passive"))
      (node (ref "U4") (pin "113") (pinfunction "PC12/SPI3_MOSI/U3_CK/U5_TX/SDIO_CK/DCMI_D9/I2S3_SD_113") (pintype "passive"))
      (node (ref "U5") (pin "5") (pinfunction "CLK_5") (pintype "passive"))
    )
    (net (code "98") (name "/PC13") (class "Default")
      (node (ref "J2") (pin "7") (pinfunction "7_7") (pintype "passive"))
      (node (ref "J6") (pin "24") (pinfunction "24_24") (pintype "passive"))
      (node (ref "U4") (pin "7") (pinfunction "PC13/RTC_AF1_7") (pintype "passive"))
    )
    (net (code "99") (name "/PC14") (class "Default")
      (node (ref "C7") (pin "2") (pinfunction "2_2") (pintype "passive"))
      (node (ref "U4") (pin "8") (pinfunction "PC14-OSC32_IN_8") (pintype "passive"))
      (node (ref "Y1") (pin "2") (pinfunction "2_2") (pintype "passive"))
    )
    (net (code "100") (name "/PC15") (class "Default")
      (node (ref "C8") (pin "2") (pinfunction "2_2") (pintype "passive"))
      (node (ref "U4") (pin "9") (pinfunction "PC15-OSC32_OUT_9") (pintype "passive"))
      (node (ref "Y1") (pin "1") (pinfunction "1_1") (pintype "passive"))
    )
    (net (code "101") (name "/PD2") (class "Default")
      (node (ref "J3") (pin "20") (pinfunction "20_20") (pintype "passive"))
      (node (ref "R32") (pin "1") (pinfunction "1_1") (pintype "passive"))
      (node (ref "U4") (pin "116") (pinfunction "PD2/TIM3_ETR/U5_RX/SDIO_CMD/DCMI_D11_116") (pintype "passive"))
      (node (ref "U5") (pin "3") (pinfunction "CMD_3") (pintype "passive"))
    )
    (net (code "102") (name "/PD3") (class "Default")
      (node (ref "J3") (pin "19") (pinfunction "19_19") (pintype "passive"))
      (node (ref "U4") (pin "117") (pinfunction "PD3/FSMC_CLK/U2_CTS_117") (pintype "passive"))
    )
    (net (code "103") (name "/PD6") (class "Default")
      (node (ref "J3") (pin "16") (pinfunction "16_16") (pintype "passive"))
      (node (ref "U4") (pin "122") (pinfunction "PD6/FSMC_NWAIT/U2_RX_122") (pintype "passive"))
    )
    (net (code "104") (name "/PD7") (class "Default")
      (node (ref "J3") (pin "15") (pinfunction "15_15") (pintype "passive"))
      (node (ref "U4") (pin "123") (pinfunction "PD7/FSMC_NE1/FSMC_NCE2/U2_CK_123") (pintype "passive"))
    )
    (net (code "105") (name "/PE2") (class "Default")
      (node (ref "J2") (pin "4") (pinfunction "4_4") (pintype "passive"))
      (node (ref "U4") (pin "1") (pinfunction "PE2/TRACECLK/FSMC_A23/ETH_MII_TXD3_1") (pintype "passive"))
    )
    (net (code "106") (name "/PF6") (class "Default")
      (node (ref "J2") (pin "16") (pinfunction "16_16") (pintype "passive"))
      (node (ref "U4") (pin "18") (pinfunction "PF6/TIM10_CH1/FSMC_NIORD/ADC3_IN4_18") (pintype "passive"))
    )
    (net (code "107") (name "/PF7") (class "Default")
      (node (ref "J2") (pin "15") (pinfunction "15_15") (pintype "passive"))
      (node (ref "U4") (pin "19") (pinfunction "PF7/TIM11_CH1/FSMC_NREG/ADC3_IN5_19") (pintype "passive"))
    )
    (net (code "108") (name "/PF8") (class "Default")
      (node (ref "J2") (pin "18") (pinfunction "18_18") (pintype "passive"))
      (node (ref "U4") (pin "20") (pinfunction "PF8/TIM13_CH1/FSMC_NIOWR/ADC3_IN6_20") (pintype "passive"))
    )
    (net (code "109") (name "/PF11") (class "Default")
      (node (ref "J2") (pin "38") (pinfunction "38_38") (pintype "passive"))
      (node (ref "J6") (pin "25") (pinfunction "25_25") (pintype "passive"))
      (node (ref "U4") (pin "49") (pinfunction "PF11/DCMI_D12_49") (pintype "passive"))
    )
    (net (code "110") (name "/PG9") (class "Default")
      (node (ref "J3") (pin "14") (pinfunction "14_14") (pintype "passive"))
      (node (ref "U4") (pin "124") (pinfunction "PG9/FSMC_NE2/FSMC_NCE3/U6_RX_124") (pintype "passive"))
    )
    (net (code "111") (name "/PG11") (class "Default")
      (node (ref "J3") (pin "12") (pinfunction "12_12") (pintype "passive"))
      (node (ref "U4") (pin "126") (pinfunction "PG11/FSMC_NCE4_2/ETH_MII_TX_EN/ETH_RMII_TX_EN_126") (pintype "passive"))
    )
    (net (code "112") (name "/PG13") (class "Default")
      (node (ref "J3") (pin "10") (pinfunction "10_10") (pintype "passive"))
      (node (ref "U4") (pin "128") (pinfunction "PG13/FSMC_A24/U6_CTS/ETH_MII_TXD0/ETH_RMII_TXD0_128") (pintype "passive"))
    )
    (net (code "113") (name "/PG14") (class "Default")
      (node (ref "J3") (pin "9") (pinfunction "9_9") (pintype "passive"))
      (node (ref "U4") (pin "129") (pinfunction "PG14/FSMC_A25/U6_TX/ETH_MII_TXD1/ETH_RMII_TXD1_129") (pintype "passive"))
    )
    (net (code "114") (name "/PG15") (class "Default")
      (node (ref "J3") (pin "8") (pinfunction "8_8") (pintype "passive"))
      (node (ref "U4") (pin "132") (pinfunction "PG15/U6_CTS/DCMI_D13_132") (pintype "passive"))
    )
    (net (code "115") (name "/RST") (class "Default")
      (node (ref "C14") (pin "2") (pinfunction "2_2") (pintype "passive"))
      (node (ref "J1") (pin "15") (pinfunction "nSRST_15") (pintype "passive"))
      (node (ref "J6") (pin "2") (pinfunction "2_2") (pintype "passive"))
      (node (ref "R24") (pin "1") (pinfunction "1_1") (pintype "passive"))
      (node (ref "RST") (pin "1") (pinfunction "C1_1") (pintype "passive"))
      (node (ref "U4") (pin "25") (pinfunction "NRST_25") (pintype "passive"))
    )
    (net (code "116") (name "/VBAT") (class "Default")
      (node (ref "C6") (pin "1") (pinfunction "1_1") (pintype "passive"))
      (node (ref "Q1") (pin "3") (pinfunction "3_3") (pintype "passive"))
      (node (ref "U4") (pin "6") (pinfunction "VBAT_6") (pintype "passive"))
    )
    (net (code "117") (name "/VREF+") (class "Default")
      (node (ref "C33") (pin "1") (pinfunction "1_1") (pintype "passive"))
      (node (ref "J2") (pin "56") (pinfunction "56_56") (pintype "passive"))
      (node (ref "R21") (pin "1") (pinfunction "1_1") (pintype "passive"))
      (node (ref "U4") (pin "32") (pinfunction "Vref+_32") (pintype "passive"))
    )
    (net (code "118") (name "3V3") (class "Default")
      (node (ref "C1") (pin "2") (pinfunction "2_2") (pintype "passive"))
      (node (ref "C13") (pin "2") (pinfunction "2_2") (pintype "passive"))
      (node (ref "C17") (pin "2") (pinfunction "2_2") (pintype "passive"))
      (node (ref "C18") (pin "2") (pinfunction "2_2") (pintype "passive"))
      (node (ref "C19") (pin "1") (pinfunction "1_1") (pintype "passive"))
      (node (ref "C2") (pin "1") (pinfunction "1_1") (pintype "passive"))
      (node (ref "C20") (pin "1") (pinfunction "1_1") (pintype "passive"))
      (node (ref "C21") (pin "1") (pinfunction "1_1") (pintype "passive"))
      (node (ref "C22") (pin "1") (pinfunction "1_1") (pintype "passive"))
      (node (ref "C23") (pin "1") (pinfunction "1_1") (pintype "passive"))
      (node (ref "C24") (pin "1") (pinfunction "1_1") (pintype "passive"))
      (node (ref "C25") (pin "1") (pinfunction "1_1") (pintype "passive"))
      (node (ref "C26") (pin "1") (pinfunction "1_1") (pintype "passive"))
      (node (ref "C27") (pin "1") (pinfunction "1_1") (pintype "passive"))
      (node (ref "C28") (pin "1") (pinfunction "1_1") (pintype "passive"))
      (node (ref "C29") (pin "1") (pinfunction "1_1") (pintype "passive"))
      (node (ref "C30") (pin "1") (pinfunction "1_1") (pintype "passive"))
      (node (ref "C31") (pin "1") (pinfunction "1_1") (pintype "passive"))
      (node (ref "C32") (pin "1") (pinfunction "1_1") (pintype "passive"))
      (node (ref "C5") (pin "1") (pinfunction "1_1") (pintype "passive"))
      (node (ref "D1") (pin "1") (pinfunction "1_1") (pintype "passive"))
      (node (ref "D2") (pin "1") (pinfunction "1_1") (pintype "passive"))
      (node (ref "D3") (pin "1") (pinfunction "1_1") (pintype "passive"))
      (node (ref "J1") (pin "1") (pinfunction "Vref_1") (pintype "passive"))
      (node (ref "J1") (pin "2") (pinfunction "Vsupply_2") (pintype "passive"))
      (node (ref "J2") (pin "59") (pinfunction "59_59") (pintype "passive"))
      (node (ref "J2") (pin "60") (pinfunction "60_60") (pintype "passive"))
      (node (ref "J3") (pin "57") (pinfunction "57_57") (pintype "passive"))
      (node (ref "J6") (pin "31") (pinfunction "31_31") (pintype "passive"))
      (node (ref "J8") (pin "2") (pinfunction "2_2") (pintype "passive"))
      (node (ref "Q1") (pin "2") (pinfunction "2_2") (pintype "passive"))
      (node (ref "Q2") (pin "2") (pinfunction "E_2") (pintype "passive"))
      (node (ref "R1") (pin "1") (pinfunction "1_1") (pintype "passive"))
      (node (ref "R2") (pin "1") (pinfunction "1_1") (pintype "passive"))
      (node (ref "R22") (pin "2") (pinfunction "2_2") (pintype "passive"))
      (node (ref "R23") (pin "1") (pinfunction "1_1") (pintype "passive"))
      (node (ref "R24") (pin "2") (pinfunction "2_2") (pintype "passive"))
      (node (ref "R28") (pin "2") (pinfunction "2_2") (pintype "passive"))
      (node (ref "R29") (pin "2") (pinfunction "2_2") (pintype "passive"))
      (node (ref "R3") (pin "1") (pinfunction "1_1") (pintype "passive"))
      (node (ref "R30") (pin "2") (pinfunction "2_2") (pintype "passive"))
      (node (ref "R31") (pin "2") (pinfunction "2_2") (pintype "passive"))
      (node (ref "R32") (pin "2") (pinfunction "2_2") (pintype "passive"))
      (node (ref "R33") (pin "2") (pinfunction "2_2") (pintype "passive"))
      (node (ref "R34") (pin "2") (pinfunction "2_2") (pintype "passive"))
      (node (ref "R35") (pin "2") (pinfunction "2_2") (pintype "passive"))
      (node (ref "R4") (pin "1") (pinfunction "1_1") (pintype "passive"))
      (node (ref "R8") (pin "2") (pinfunction "2_2") (pintype "passive"))
      (node (ref "U1") (pin "2") (pinfunction "OUT_2") (pintype "passive"))
      (node (ref "U2") (pin "11") (pinfunction "VDD_11") (pintype "passive"))
      (node (ref "U2") (pin "33") (pinfunction "VDD_33") (pintype "passive"))
      (node (ref "U3") (pin "3") (pinfunction "WP_3") (pintype "passive"))
      (node (ref "U3") (pin "7") (pinfunction "HOLD_7") (pintype "passive"))
      (node (ref "U3") (pin "8") (pinfunction "VCC_8") (pintype "passive"))
      (node (ref "U4") (pin "108") (pinfunction "VDD_108") (pintype "passive"))
      (node (ref "U4") (pin "121") (pinfunction "VDD_121") (pintype "passive"))
      (node (ref "U4") (pin "131") (pinfunction "VDD_131") (pintype "passive"))
      (node (ref "U4") (pin "144") (pinfunction "VDD_144") (pintype "passive"))
      (node (ref "U4") (pin "17") (pinfunction "VDD_17") (pintype "passive"))
      (node (ref "U4") (pin "30") (pinfunction "VDD_30") (pintype "passive"))
      (node (ref "U4") (pin "39") (pinfunction "VDD_39") (pintype "passive"))
      (node (ref "U4") (pin "52") (pinfunction "VDD_52") (pintype "passive"))
      (node (ref "U4") (pin "62") (pinfunction "VDD_62") (pintype "passive"))
      (node (ref "U4") (pin "72") (pinfunction "VDD_72") (pintype "passive"))
      (node (ref "U4") (pin "84") (pinfunction "VDD_84") (pintype "passive"))
      (node (ref "U4") (pin "95") (pinfunction "VDD_95") (pintype "passive"))
      (node (ref "U5") (pin "4") (pinfunction "VCC_4") (pintype "passive"))
      (node (ref "WK_UP") (pin "1") (pinfunction "C1_1") (pintype "passive"))
    )
    (net (code "119") (name "5V") (class "Default")
      (node (ref "C3") (pin "1") (pinfunction "1_1") (pintype "passive"))
      (node (ref "C4") (pin "1") (pinfunction "1_1") (pintype "passive"))
      (node (ref "J3") (pin "59") (pinfunction "59_59") (pintype "passive"))
      (node (ref "J5") (pin "1") (pinfunction "1_1") (pintype "passive"))
      (node (ref "R5") (pin "1") (pinfunction "1_1") (pintype "passive"))
      (node (ref "U1") (pin "3") (pinfunction "VCC_3") (pintype "passive"))
    )
    (net (code "120") (name "GND") (class "Default")
      (node (ref "B1") (pin "2") (pinfunction "-_2") (pintype "passive"))
      (node (ref "C1") (pin "1") (pinfunction "1_1") (pintype "passive"))
      (node (ref "C10") (pin "2") (pinfunction "2_2") (pintype "passive"))
      (node (ref "C11") (pin "2") (pinfunction "2_2") (pintype "passive"))
      (node (ref "C12") (pin "2") (pinfunction "2_2") (pintype "passive"))
      (node (ref "C13") (pin "1") (pinfunction "1_1") (pintype "passive"))
      (node (ref "C14") (pin "1") (pinfunction "1_1") (pintype "passive"))
      (node (ref "C15") (pin "1") (pinfunction "1_1") (pintype "passive"))
      (node (ref "C16") (pin "1") (pinfunction "1_1") (pintype "passive"))
      (node (ref "C17") (pin "1") (pinfunction "1_1") (pintype "passive"))
      (node (ref "C18") (pin "1") (pinfunction "1_1") (pintype "passive"))
      (node (ref "C19") (pin "2") (pinfunction "2_2") (pintype "passive"))
      (node (ref "C2") (pin "2") (pinfunction "2_2") (pintype "passive"))
      (node (ref "C20") (pin "2") (pinfunction "2_2") (pintype "passive"))
      (node (ref "C21") (pin "2") (pinfunction "2_2") (pintype "passive"))
      (node (ref "C22") (pin "2") (pinfunction "2_2") (pintype "passive"))
      (node (ref "C23") (pin "2") (pinfunction "2_2") (pintype "passive"))
      (node (ref "C24") (pin "2") (pinfunction "2_2") (pintype "passive"))
      (node (ref "C25") (pin "2") (pinfunction "2_2") (pintype "passive"))
      (node (ref "C26") (pin "2") (pinfunction "2_2") (pintype "passive"))
      (node (ref "C27") (pin "2") (pinfunction "2_2") (pintype "passive"))
      (node (ref "C28") (pin "2") (pinfunction "2_2") (pintype "passive"))
      (node (ref "C29") (pin "2") (pinfunction "2_2") (pintype "passive"))
      (node (ref "C3") (pin "2") (pinfunction "2_2") (pintype "passive"))
      (node (ref "C30") (pin "2") (pinfunction "2_2") (pintype "passive"))
      (node (ref "C31") (pin "2") (pinfunction "2_2") (pintype "passive"))
      (node (ref "C32") (pin "2") (pinfunction "2_2") (pintype "passive"))
      (node (ref "C33") (pin "2") (pinfunction "2_2") (pintype "passive"))
      (node (ref "C4") (pin "2") (pinfunction "2_2") (pintype "passive"))
      (node (ref "C5") (pin "2") (pinfunction "2_2") (pintype "passive"))
      (node (ref "C6") (pin "2") (pinfunction "2_2") (pintype "passive"))
      (node (ref "C7") (pin "1") (pinfunction "1_1") (pintype "passive"))
      (node (ref "C8") (pin "1") (pinfunction "1_1") (pintype "passive"))
      (node (ref "C9") (pin "2") (pinfunction "2_2") (pintype "passive"))
      (node (ref "J1") (pin "10") (pinfunction "GND_10") (pintype "passive"))
      (node (ref "J1") (pin "12") (pinfunction "GND_12") (pintype "passive"))
      (node (ref "J1") (pin "14") (pinfunction "GND_14") (pintype "passive"))
      (node (ref "J1") (pin "16") (pinfunction "GND_16") (pintype "passive"))
      (node (ref "J1") (pin "18") (pinfunction "GND_18") (pintype "passive"))
      (node (ref "J1") (pin "20") (pinfunction "GND_20") (pintype "passive"))
      (node (ref "J1") (pin "4") (pinfunction "GND_4") (pintype "passive"))
      (node (ref "J1") (pin "6") (pinfunction "GND_6") (pintype "passive"))
      (node (ref "J1") (pin "8") (pinfunction "GND_8") (pintype "passive"))
      (node (ref "J2") (pin "55") (pinfunction "55_55") (pintype "passive"))
      (node (ref "J3") (pin "58") (pinfunction "58_58") (pintype "passive"))
      (node (ref "J3") (pin "60") (pinfunction "60_60") (pintype "passive"))
      (node (ref "J4") (pin "5") (pinfunction "GND_5") (pintype "passive"))
      (node (ref "J5") (pin "2") (pinfunction "2_2") (pintype "passive"))
      (node (ref "J6") (pin "1") (pinfunction "1_1") (pintype "passive"))
      (node (ref "J6") (pin "30") (pinfunction "30_30") (pintype "passive"))
      (node (ref "J6") (pin "32") (pinfunction "32_32") (pintype "passive"))
      (node (ref "J8") (pin "1") (pinfunction "1_1") (pintype "passive"))
      (node (ref "K0") (pin "1") (pinfunction "C1_1") (pintype "passive"))
      (node (ref "K1") (pin "1") (pinfunction "C1_1") (pintype "passive"))
      (node (ref "R12") (pin "2") (pinfunction "2_2") (pintype "passive"))
      (node (ref "R18") (pin "2") (pinfunction "2_2") (pintype "passive"))
      (node (ref "R19") (pin "2") (pinfunction "2_2") (pintype "passive"))
      (node (ref "R25") (pin "2") (pinfunction "2_2") (pintype "passive"))
      (node (ref "R26") (pin "2") (pinfunction "2_2") (pintype "passive"))
      (node (ref "R9") (pin "1") (pinfunction "1_1") (pintype "passive"))
      (node (ref "RST") (pin "2") (pinfunction "C2_2") (pintype "passive"))
      (node (ref "U1") (pin "1") (pinfunction "GND_1") (pintype "passive"))
      (node (ref "U2") (pin "12") (pinfunction "GND_12") (pintype "passive"))
      (node (ref "U2") (pin "34") (pinfunction "GND_34") (pintype "passive"))
      (node (ref "U3") (pin "4") (pinfunction "GND_4") (pintype "passive"))
      (node (ref "U4") (pin "107") (pinfunction "VSS_107") (pintype "passive"))
      (node (ref "U4") (pin "120") (pinfunction "VSS_120") (pintype "passive"))
      (node (ref "U4") (pin "130") (pinfunction "VSS_130") (pintype "passive"))
      (node (ref "U4") (pin "16") (pinfunction "VSS_16") (pintype "passive"))
      (node (ref "U4") (pin "31") (pinfunction "VSSA_31") (pintype "passive"))
      (node (ref "U4") (pin "38") (pinfunction "VSS_38") (pintype "passive"))
      (node (ref "U4") (pin "51") (pinfunction "VSS_51") (pintype "passive"))
      (node (ref "U4") (pin "61") (pinfunction "VSS_61") (pintype "passive"))
      (node (ref "U4") (pin "83") (pinfunction "VSS_83") (pintype "passive"))
      (node (ref "U4") (pin "94") (pinfunction "VSS_94") (pintype "passive"))
      (node (ref "U5") (pin "6") (pinfunction "GND_6") (pintype "passive"))
      (node (ref "U5") (pin "9") (pinfunction "NC_9") (pintype "passive"))
    )
    (net (code "121") (name "Net-(B1-+)") (class "Default")
      (node (ref "B1") (pin "1") (pinfunction "+_1") (pintype "passive"))
      (node (ref "Q1") (pin "1") (pinfunction "1_1") (pintype "passive"))
    )
    (net (code "122") (name "Net-(D1-Pad2)") (class "Default")
      (node (ref "D1") (pin "2") (pinfunction "2_2") (pintype "passive"))
      (node (ref "R14") (pin "1") (pinfunction "1_1") (pintype "passive"))
    )
    (net (code "123") (name "Net-(D2-Pad2)") (class "Default")
      (node (ref "D2") (pin "2") (pinfunction "2_2") (pintype "passive"))
      (node (ref "R16") (pin "1") (pinfunction "1_1") (pintype "passive"))
    )
    (net (code "124") (name "Net-(D3-Pad2)") (class "Default")
      (node (ref "D3") (pin "2") (pinfunction "2_2") (pintype "passive"))
      (node (ref "R19") (pin "1") (pinfunction "1_1") (pintype "passive"))
    )
    (net (code "125") (name "Net-(J2-Pad57)") (class "Default")
      (node (ref "J2") (pin "57") (pinfunction "57_57") (pintype "passive"))
      (node (ref "R10") (pin "1") (pinfunction "1_1") (pintype "passive"))
    )
    (net (code "126") (name "Net-(J4-D+)") (class "Default")
      (node (ref "J4") (pin "3") (pinfunction "D+_3") (pintype "passive"))
      (node (ref "R7") (pin "1") (pinfunction "1_1") (pintype "passive"))
      (node (ref "R8") (pin "1") (pinfunction "1_1") (pintype "passive"))
    )
    (net (code "127") (name "Net-(J4-D-)") (class "Default")
      (node (ref "J4") (pin "2") (pinfunction "D-_2") (pintype "passive"))
      (node (ref "R6") (pin "1") (pinfunction "1_1") (pintype "passive"))
    )
    (net (code "128") (name "Net-(J4-VDD)") (class "Default")
      (node (ref "J4") (pin "1") (pinfunction "VDD_1") (pintype "passive"))
      (node (ref "R5") (pin "2") (pinfunction "2_2") (pintype "passive"))
    )
    (net (code "129") (name "Net-(J6-Pad27)") (class "Default")
      (node (ref "J6") (pin "27") (pinfunction "27_27") (pintype "passive"))
      (node (ref "R17") (pin "1") (pinfunction "1_1") (pintype "passive"))
    )
    (net (code "130") (name "Net-(Q2-B)") (class "Default")
      (node (ref "Q2") (pin "1") (pinfunction "B_1") (pintype "passive"))
      (node (ref "R13") (pin "1") (pinfunction "1_1") (pintype "passive"))
      (node (ref "R15") (pin "2") (pinfunction "2_2") (pintype "passive"))
    )
    (net (code "131") (name "Net-(Q2-C)") (class "Default")
      (node (ref "J6") (pin "28") (pinfunction "28_28") (pintype "passive"))
      (node (ref "Q2") (pin "3") (pinfunction "C_3") (pintype "passive"))
      (node (ref "R15") (pin "1") (pinfunction "1_1") (pintype "passive"))
      (node (ref "R18") (pin "1") (pinfunction "1_1") (pintype "passive"))
    )
    (net (code "132") (name "Net-(U3-CLK)") (class "Default")
      (node (ref "R27") (pin "1") (pinfunction "1_1") (pintype "passive"))
      (node (ref "U3") (pin "6") (pinfunction "CLK_6") (pintype "passive"))
    )
    (net (code "133") (name "Net-(U4-PDR_ON)") (class "Default")
      (node (ref "R26") (pin "1") (pinfunction "1_1") (pintype "passive"))
      (node (ref "R28") (pin "1") (pinfunction "1_1") (pintype "passive"))
      (node (ref "U4") (pin "143") (pinfunction "PDR_ON_143") (pintype "passive"))
    )
    (net (code "134") (name "Net-(U4-PH0-OSC_IN)") (class "Default")
      (node (ref "C10") (pin "1") (pinfunction "1_1") (pintype "passive"))
      (node (ref "R20") (pin "1") (pinfunction "1_1") (pintype "passive"))
      (node (ref "U4") (pin "23") (pinfunction "PH0-OSC_IN_23") (pintype "passive"))
      (node (ref "Y2") (pin "1") (pinfunction "1_1") (pintype "passive"))
    )
    (net (code "135") (name "Net-(U4-PH1-OSC_OUT)") (class "Default")
      (node (ref "C9") (pin "1") (pinfunction "1_1") (pintype "passive"))
      (node (ref "R20") (pin "2") (pinfunction "2_2") (pintype "passive"))
      (node (ref "U4") (pin "24") (pinfunction "PH1-OSC_OUT_24") (pintype "passive"))
      (node (ref "Y2") (pin "2") (pinfunction "2_2") (pintype "passive"))
    )
    (net (code "136") (name "Net-(U4-Vcap_1)") (class "Default")
      (node (ref "C11") (pin "1") (pinfunction "1_1") (pintype "passive"))
      (node (ref "U4") (pin "71") (pinfunction "Vcap_1_71") (pintype "passive"))
    )
    (net (code "137") (name "Net-(U4-Vcap_2)") (class "Default")
      (node (ref "C12") (pin "1") (pinfunction "1_1") (pintype "passive"))
      (node (ref "U4") (pin "106") (pinfunction "Vcap_2_106") (pintype "passive"))
    )
    (net (code "138") (name "VDDA") (class "Default")
      (node (ref "C15") (pin "2") (pinfunction "2_2") (pintype "passive"))
      (node (ref "C16") (pin "2") (pinfunction "2_2") (pintype "passive"))
      (node (ref "R21") (pin "2") (pinfunction "2_2") (pintype "passive"))
      (node (ref "R22") (pin "1") (pinfunction "1_1") (pintype "passive"))
      (node (ref "U4") (pin "33") (pinfunction "VDDA_33") (pintype "passive"))
    )
    (net (code "139") (name "unconnected-(J1-NC-Pad17)") (class "Default")
      (node (ref "J1") (pin "17") (pinfunction "NC_17") (pintype "passive"))
    )
    (net (code "140") (name "unconnected-(J1-NC-Pad19)") (class "Default")
      (node (ref "J1") (pin "19") (pinfunction "NC_19") (pintype "passive"))
    )
    (net (code "141") (name "unconnected-(J1-RTCK-Pad11)") (class "Default")
      (node (ref "J1") (pin "11") (pinfunction "RTCK_11") (pintype "passive"))
    )
    (net (code "142") (name "unconnected-(J4-NCC-Pad4)") (class "Default")
      (node (ref "J4") (pin "4") (pinfunction "NCC_4") (pintype "passive"))
    )
    (net (code "143") (name "unconnected-(J6-Pad29)") (class "Default")
      (node (ref "J6") (pin "29") (pinfunction "29_29") (pintype "passive"))
    )
  )
)
